# SFP_PortB.net
KiCad netlist of a schematic drawn in Altium Designer
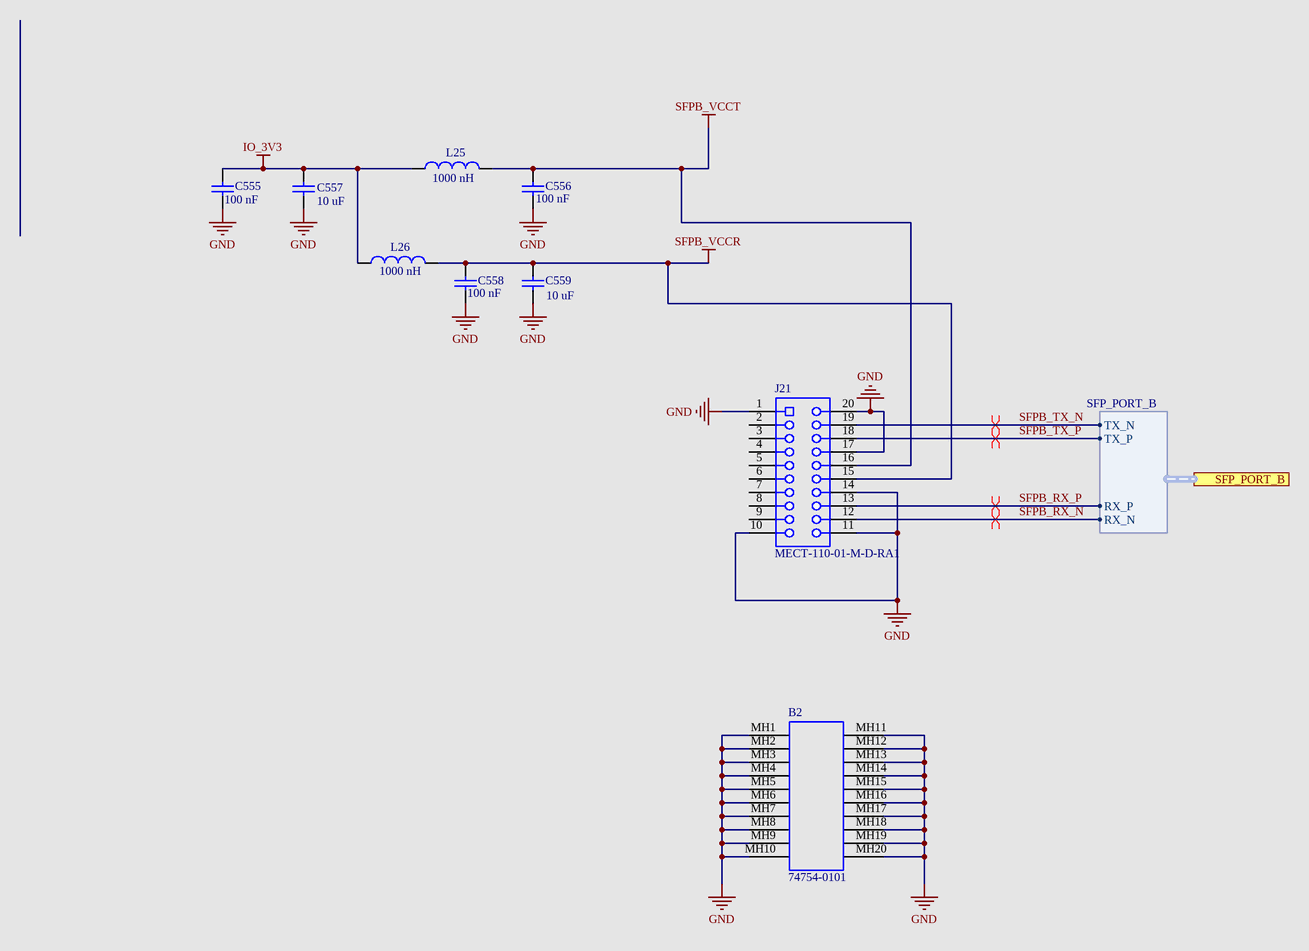
[diagram p0: SFP_PortB.SchDoc]

(export (version "E")
  (design (tool "Eeschema 10.0.6"))
  (components
    (comp (ref "B2")
      (value "74754-0101")
      (footprint "MOLX-74754-0101_V")
      (description "SFP+ Cage, Single Port, Height 10.85 mm, Tail Height 3.05 mm, -40 to 85 degC, RoHS, Tray")
      (fields (field (name "MANUFACTURER") "Molex"))
      (libsource (lib "Altium Content Vault") (part "MOLX-74754-0101"))
    )
    (comp (ref "C555")
      (value "C1005X7R1E104M")
      (footprint "CAPC1005X55X10LL05")
      (description "Chip Capacitor, 0.1 uF, +/- 20%, 25 V, -55 to 125 degC, 0402 (1005 Metric), RoHS, Tape and Reel")
      (fields (field (name "TOLERANCE") "20%") (field (name "CAPACITANCE") "100 nF"))
      (libsource (lib "Altium Content Vault") (part "CAP-NP-2"))
    )
    (comp (ref "C556")
      (value "C1005X7R1E104M")
      (footprint "CAPC1005X55X10LL05")
      (description "Chip Capacitor, 0.1 uF, +/- 20%, 25 V, -55 to 125 degC, 0402 (1005 Metric), RoHS, Tape and Reel")
      (fields (field (name "TOLERANCE") "20%") (field (name "CAPACITANCE") "100 nF"))
      (libsource (lib "Altium Content Vault") (part "CAP-NP-2"))
    )
    (comp (ref "C557")
      (value "C2012X5R1C106K085AC")
      (footprint "CAPC2013X100X20NL20")
      (description "Chip Capacitor, 10 uF, +/- 10%, 16 V, -55 to 85 degC, 0805 (2012 Metric), RoHS, Tape and Reel")
      (fields (field (name "TOLERANCE") "10%") (field (name "CAPACITANCE") "10 uF"))
      (libsource (lib "") (part "CAP-NP-2_1"))
    )
    (comp (ref "C558")
      (value "C1005X7R1E104M")
      (footprint "CAPC1005X55X10LL05")
      (description "Chip Capacitor, 0.1 uF, +/- 20%, 25 V, -55 to 125 degC, 0402 (1005 Metric), RoHS, Tape and Reel")
      (fields (field (name "TOLERANCE") "20%") (field (name "CAPACITANCE") "100 nF"))
      (libsource (lib "Altium Content Vault") (part "CAP-NP-2"))
    )
    (comp (ref "C559")
      (value "C2012X5R1C106K085AC")
      (footprint "CAPC2013X100X20NL20")
      (description "Chip Capacitor, 10 uF, +/- 10%, 16 V, -55 to 85 degC, 0805 (2012 Metric), RoHS, Tape and Reel")
      (fields (field (name "TOLERANCE") "10%") (field (name "CAPACITANCE") "10 uF"))
      (libsource (lib "") (part "CAP-NP-2_1"))
    )
    (comp (ref "J21")
      (value "MECT-110-01-M-D-RA1")
      (footprint "SMTC-MECT-110-01-M-D-RA1_V")
      (fields (field (name "MANUFACTURER") "Samtec"))
      (libsource (lib "Altium Content Vault") (part "CMP-1707-00001-1"))
    )
    (comp (ref "L25")
      (value "1008CS-102XFLC")
      (footprint "COIL-1008CS_V")
      (description "Chip Inductor, 1000 nH, +/- 1%, -40 to 125 degC, 2-Pin SMD, RoHS, Tape and Reel")
      (fields (field (name "INDUCTANCE") "1000 nH"))
      (libsource (lib "Altium Content Vault") (part "IND-2"))
    )
    (comp (ref "L26")
      (value "1008CS-102XFLC")
      (footprint "COIL-1008CS_V")
      (description "Chip Inductor, 1000 nH, +/- 1%, -40 to 125 degC, 2-Pin SMD, RoHS, Tape and Reel")
      (fields (field (name "INDUCTANCE") "1000 nH"))
      (libsource (lib "Altium Content Vault") (part "IND-2"))
    )
  )
  (nets
    (net (code "2") (name "/SFPB_RX_N") (class "Default")
      (node (ref "J21") (pin "12") (pinfunction "12_12") (pintype "passive"))
    )
    (net (code "3") (name "/SFPB_RX_P") (class "Default")
      (node (ref "J21") (pin "13") (pinfunction "13_13") (pintype "passive"))
    )
    (net (code "4") (name "/SFPB_TX_N") (class "Default")
      (node (ref "J21") (pin "19") (pinfunction "19_19") (pintype "passive"))
    )
    (net (code "5") (name "/SFPB_TX_P") (class "Default")
      (node (ref "J21") (pin "18") (pinfunction "18_18") (pintype "passive"))
    )
    (net (code "7") (name "GND") (class "Default")
      (node (ref "B2") (pin "MH1") (pinfunction "MH1_MH1") (pintype "passive"))
      (node (ref "B2") (pin "MH10") (pinfunction "MH10_MH10") (pintype "passive"))
      (node (ref "B2") (pin "MH11") (pinfunction "MH11_MH11") (pintype "passive"))
      (node (ref "B2") (pin "MH12") (pinfunction "MH12_MH12") (pintype "passive"))
      (node (ref "B2") (pin "MH13") (pinfunction "MH13_MH13") (pintype "passive"))
      (node (ref "B2") (pin "MH14") (pinfunction "MH14_MH14") (pintype "passive"))
      (node (ref "B2") (pin "MH15") (pinfunction "MH15_MH15") (pintype "passive"))
      (node (ref "B2") (pin "MH16") (pinfunction "MH16_MH16") (pintype "passive"))
      (node (ref "B2") (pin "MH17") (pinfunction "MH17_MH17") (pintype "passive"))
      (node (ref "B2") (pin "MH18") (pinfunction "MH18_MH18") (pintype "passive"))
      (node (ref "B2") (pin "MH19") (pinfunction "MH19_MH19") (pintype "passive"))
      (node (ref "B2") (pin "MH2") (pinfunction "MH2_MH2") (pintype "passive"))
      (node (ref "B2") (pin "MH20") (pinfunction "MH20_MH20") (pintype "passive"))
      (node (ref "B2") (pin "MH3") (pinfunction "MH3_MH3") (pintype "passive"))
      (node (ref "B2") (pin "MH4") (pinfunction "MH4_MH4") (pintype "passive"))
      (node (ref "B2") (pin "MH5") (pinfunction "MH5_MH5") (pintype "passive"))
      (node (ref "B2") (pin "MH6") (pinfunction "MH6_MH6") (pintype "passive"))
      (node (ref "B2") (pin "MH7") (pinfunction "MH7_MH7") (pintype "passive"))
      (node (ref "B2") (pin "MH8") (pinfunction "MH8_MH8") (pintype "passive"))
      (node (ref "B2") (pin "MH9") (pinfunction "MH9_MH9") (pintype "passive"))
      (node (ref "C555") (pin "1") (pinfunction "1_1") (pintype "passive"))
      (node (ref "C556") (pin "1") (pinfunction "1_1") (pintype "passive"))
      (node (ref "C557") (pin "1") (pinfunction "1_1") (pintype "passive"))
      (node (ref "C558") (pin "1") (pinfunction "1_1") (pintype "passive"))
      (node (ref "C559") (pin "1") (pinfunction "1_1") (pintype "passive"))
      (node (ref "J21") (pin "1") (pinfunction "1_1") (pintype "passive"))
      (node (ref "J21") (pin "10") (pinfunction "10_10") (pintype "passive"))
      (node (ref "J21") (pin "11") (pinfunction "11_11") (pintype "passive"))
      (node (ref "J21") (pin "14") (pinfunction "14_14") (pintype "passive"))
      (node (ref "J21") (pin "17") (pinfunction "17_17") (pintype "passive"))
      (node (ref "J21") (pin "20") (pinfunction "20_20") (pintype "passive"))
    )
    (net (code "8") (name "IO_3V3") (class "Default")
      (node (ref "C555") (pin "2") (pinfunction "2_2") (pintype "passive"))
      (node (ref "C557") (pin "2") (pinfunction "2_2") (pintype "passive"))
      (node (ref "L25") (pin "1") (pinfunction "1_1") (pintype "passive"))
      (node (ref "L26") (pin "1") (pinfunction "1_1") (pintype "passive"))
    )
    (net (code "9") (name "SFPB_VCCR") (class "Default")
      (node (ref "C558") (pin "2") (pinfunction "2_2") (pintype "passive"))
      (node (ref "C559") (pin "2") (pinfunction "2_2") (pintype "passive"))
      (node (ref "J21") (pin "15") (pinfunction "15_15") (pintype "passive"))
      (node (ref "L26") (pin "2") (pinfunction "2_2") (pintype "passive"))
    )
    (net (code "10") (name "SFPB_VCCT") (class "Default")
      (node (ref "C556") (pin "2") (pinfunction "2_2") (pintype "passive"))
      (node (ref "J21") (pin "16") (pinfunction "16_16") (pintype "passive"))
      (node (ref "L25") (pin "2") (pinfunction "2_2") (pintype "passive"))
    )
    (net (code "11") (name "unconnected-(J21-Pad2)") (class "Default")
      (node (ref "J21") (pin "2") (pinfunction "2_2") (pintype "passive"))
    )
    (net (code "12") (name "unconnected-(J21-Pad3)") (class "Default")
      (node (ref "J21") (pin "3") (pinfunction "3_3") (pintype "passive"))
    )
    (net (code "13") (name "unconnected-(J21-Pad4)") (class "Default")
      (node (ref "J21") (pin "4") (pinfunction "4_4") (pintype "passive"))
    )
    (net (code "14") (name "unconnected-(J21-Pad5)") (class "Default")
      (node (ref "J21") (pin "5") (pinfunction "5_5") (pintype "passive"))
    )
    (net (code "15") (name "unconnected-(J21-Pad6)") (class "Default")
      (node (ref "J21") (pin "6") (pinfunction "6_6") (pintype "passive"))
    )
    (net (code "16") (name "unconnected-(J21-Pad7)") (class "Default")
      (node (ref "J21") (pin "7") (pinfunction "7_7") (pintype "passive"))
    )
    (net (code "17") (name "unconnected-(J21-Pad8)") (class "Default")
      (node (ref "J21") (pin "8") (pinfunction "8_8") (pintype "passive"))
    )
    (net (code "18") (name "unconnected-(J21-Pad9)") (class "Default")
      (node (ref "J21") (pin "9") (pinfunction "9_9") (pintype "passive"))
    )
  )
)
